# entireboard_v2_4layer.net
KiCad netlist of a schematic drawn in EAGLE
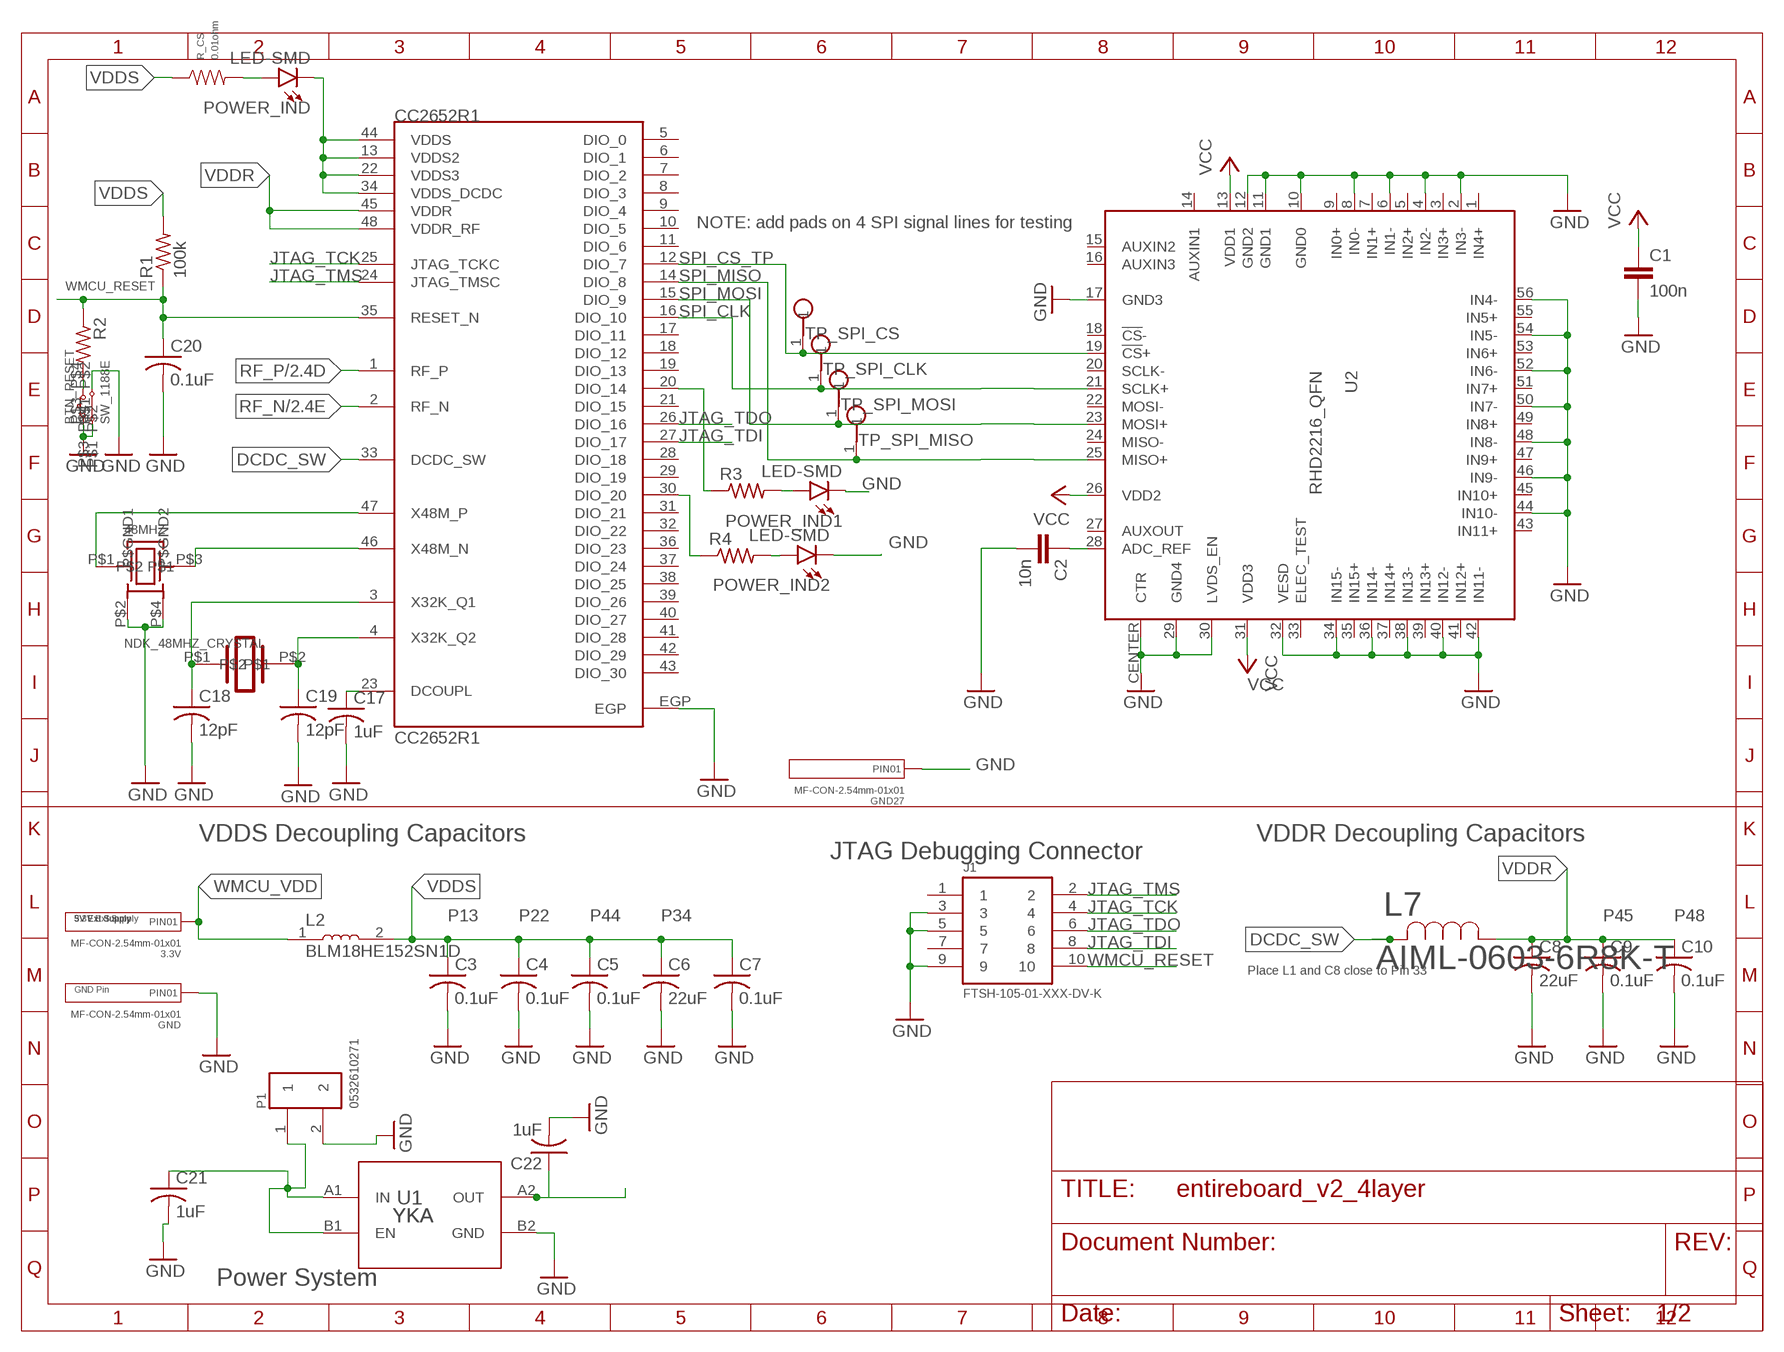
[diagram p0: schematic, sheet 1]
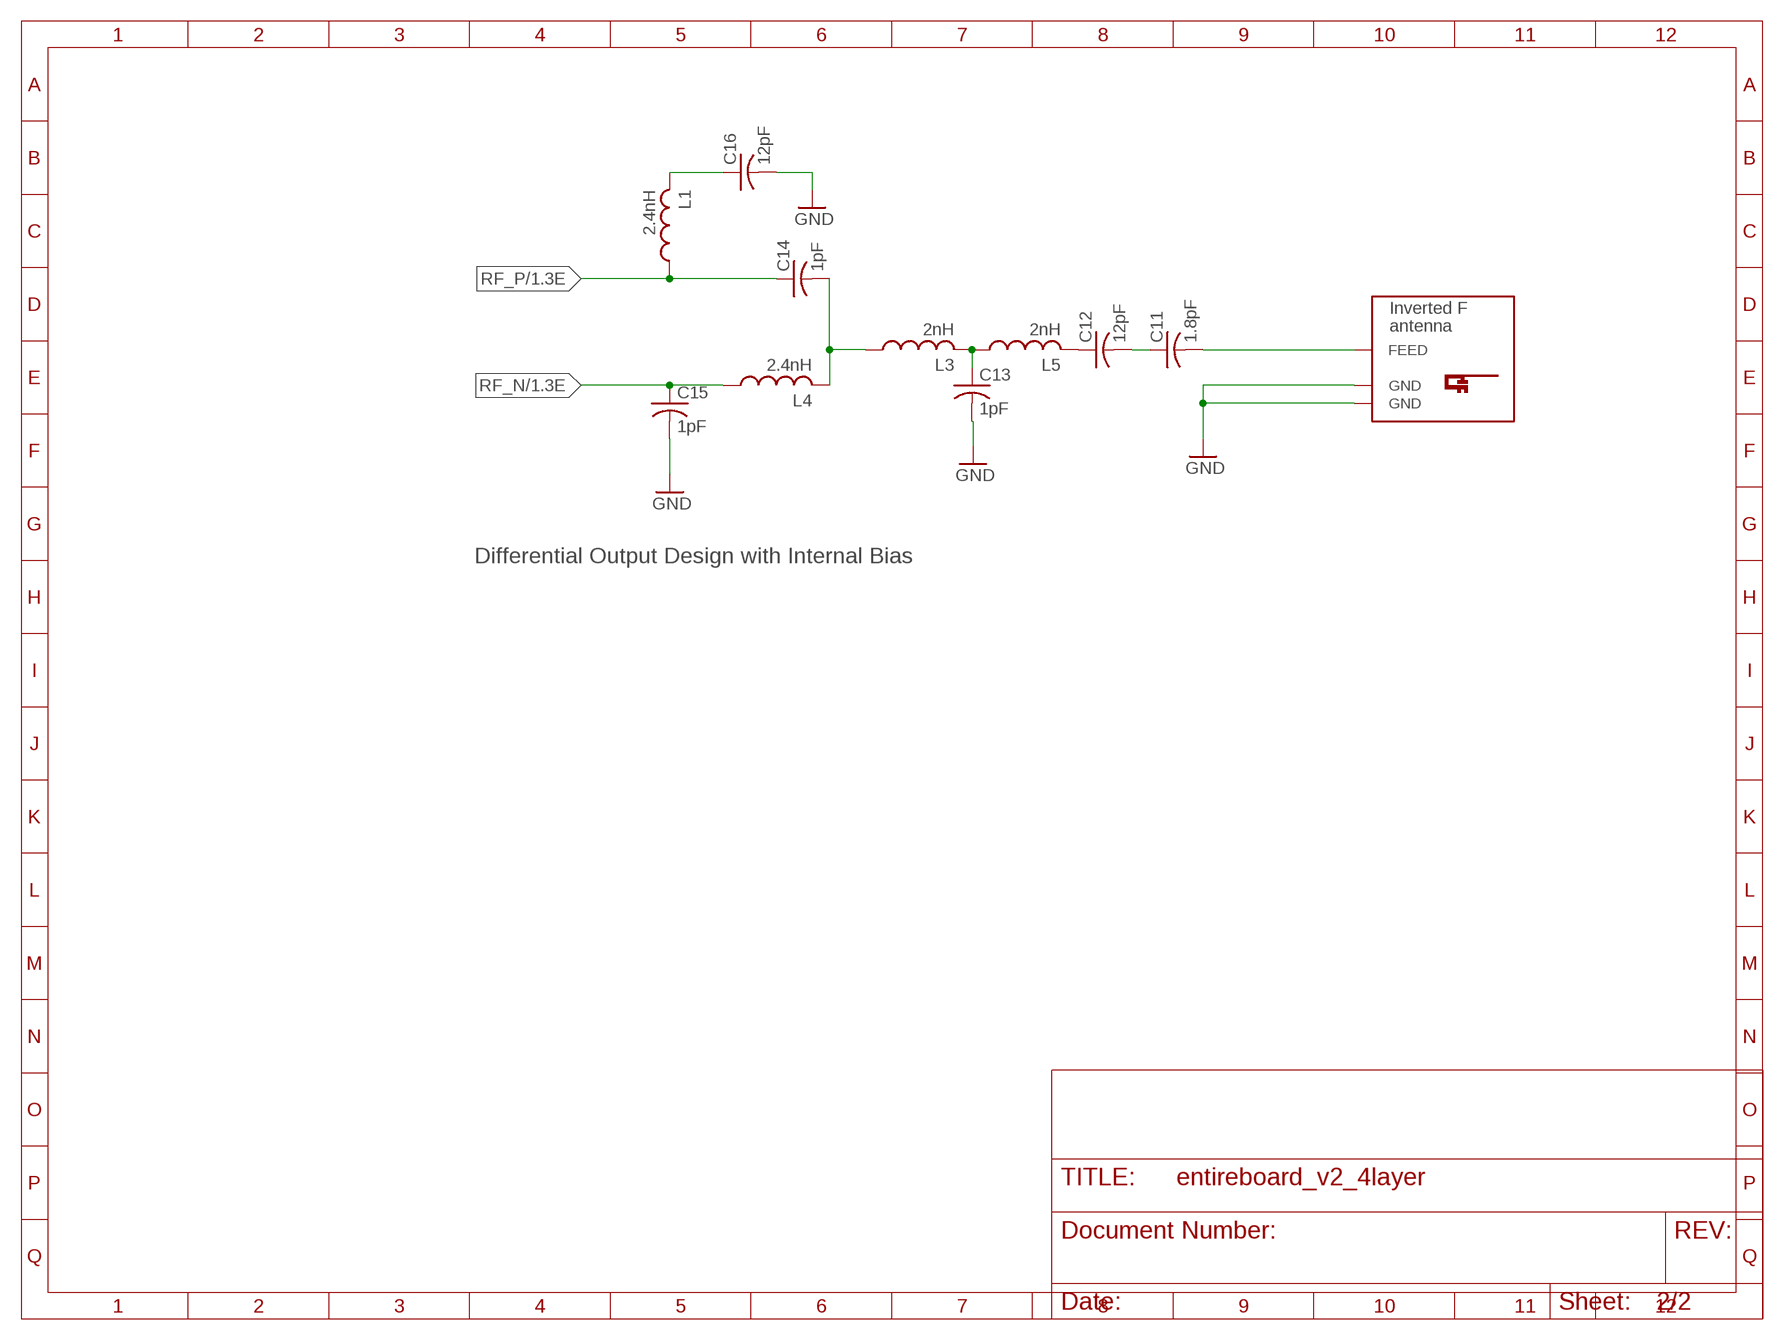
[diagram p1: schematic, sheet 2]

(export (version "E")
  (design (tool "Eeschema 10.0.6"))
  (components
    (comp (ref "C11")
      (value "1.8pF")
      (footprint "eagle-import:C0402")
      (libsource (lib "eagle-import") (part "C-USC0402"))
    )
    (comp (ref "C12")
      (value "12pF")
      (footprint "eagle-import:C0402")
      (libsource (lib "eagle-import") (part "C-USC0402"))
    )
    (comp (ref "C13")
      (value "1pF")
      (footprint "eagle-import:C0402")
      (libsource (lib "eagle-import") (part "C-USC0402"))
    )
    (comp (ref "C14")
      (value "1pF")
      (footprint "eagle-import:C0402")
      (libsource (lib "eagle-import") (part "C-USC0402"))
    )
    (comp (ref "C15")
      (value "1pF")
      (footprint "eagle-import:C0402")
      (libsource (lib "eagle-import") (part "C-USC0402"))
    )
    (comp (ref "C16")
      (value "12pF")
      (footprint "eagle-import:C0402")
      (libsource (lib "eagle-import") (part "C-USC0402"))
    )
    (comp (ref "L1")
      (value "2.4nH")
      (footprint "eagle-import:L0201")
      (libsource (lib "eagle-import") (part "L-USL0201"))
    )
    (comp (ref "L3")
      (value "2nH")
      (footprint "eagle-import:L0201")
      (libsource (lib "eagle-import") (part "L-USL0201"))
    )
    (comp (ref "L4")
      (value "2.4nH")
      (footprint "eagle-import:L0201")
      (libsource (lib "eagle-import") (part "L-USL0201"))
    )
    (comp (ref "L5")
      (value "2nH")
      (footprint "eagle-import:L0201")
      (libsource (lib "eagle-import") (part "L-USL0201"))
    )
    (comp (ref "U$2")
      (value "INVERTED_F_ANTENNA+0")
      (footprint "eagle-import:DN007+0")
      (libsource (lib "eagle-import") (part "INVERTED_F_ANTENNA+0"))
    )
    (comp (ref "3.3V")
      (value "MF-CON-2.54mm-01x01")
      (footprint "eagle-import:PTH_2.54MM_01X01")
      (fields (field (name "HOUSEPART") "YES"))
      (libsource (lib "eagle-import") (part "CON_01X01_PTH_2.54MM"))
    )
    (comp (ref "38.768KHZ")
      (value "EPSON_32.768KHZ_CRYSTAL")
      (footprint "eagle-import:2-SMD")
      (libsource (lib "eagle-import") (part "EPSON_32.768KHZ_CRYSTAL"))
    )
    (comp (ref "48MHZ")
      (value "NDK_48MHZ_CRYSTAL")
      (footprint "eagle-import:4-SMD")
      (libsource (lib "eagle-import") (part "NDK_48MHZ_CRYSTAL"))
    )
    (comp (ref "BTN_RESET")
      (value "SW_1188E")
      (footprint "eagle-import:SW_1188E")
      (libsource (lib "eagle-import") (part "SW_1188E"))
    )
    (comp (ref "C1")
      (value "100n")
      (footprint "eagle-import:0402")
      (libsource (lib "eagle-import") (part "C_0402"))
    )
    (comp (ref "C2")
      (value "10n")
      (footprint "eagle-import:0402")
      (libsource (lib "eagle-import") (part "C_0402"))
    )
    (comp (ref "C3")
      (value "0.1uF")
      (footprint "eagle-import:C0402")
      (libsource (lib "eagle-import") (part "C-USC0402"))
    )
    (comp (ref "C4")
      (value "0.1uF")
      (footprint "eagle-import:C0402")
      (libsource (lib "eagle-import") (part "C-USC0402"))
    )
    (comp (ref "C5")
      (value "0.1uF")
      (footprint "eagle-import:C0402")
      (libsource (lib "eagle-import") (part "C-USC0402"))
    )
    (comp (ref "C6")
      (value "22uF")
      (footprint "eagle-import:C0402")
      (libsource (lib "eagle-import") (part "C-USC0402"))
    )
    (comp (ref "C7")
      (value "0.1uF")
      (footprint "eagle-import:C0402")
      (libsource (lib "eagle-import") (part "C-USC0402"))
    )
    (comp (ref "C8")
      (value "22uF")
      (footprint "eagle-import:C0402")
      (libsource (lib "eagle-import") (part "C-USC0402"))
    )
    (comp (ref "C9")
      (value "0.1uF")
      (footprint "eagle-import:C0402")
      (libsource (lib "eagle-import") (part "C-USC0402"))
    )
    (comp (ref "C10")
      (value "0.1uF")
      (footprint "eagle-import:C0402")
      (libsource (lib "eagle-import") (part "C-USC0402"))
    )
    (comp (ref "C17")
      (value "1uF")
      (footprint "eagle-import:C0402")
      (libsource (lib "eagle-import") (part "C-USC0402"))
    )
    (comp (ref "C18")
      (value "12pF")
      (footprint "eagle-import:C0402")
      (libsource (lib "eagle-import") (part "C-USC0402"))
    )
    (comp (ref "C19")
      (value "12pF")
      (footprint "eagle-import:C0402")
      (libsource (lib "eagle-import") (part "C-USC0402"))
    )
    (comp (ref "C20")
      (value "0.1uF")
      (footprint "eagle-import:C0402")
      (libsource (lib "eagle-import") (part "C-USC0402"))
    )
    (comp (ref "C21")
      (value "1uF")
      (footprint "eagle-import:C0402")
      (libsource (lib "eagle-import") (part "C-USC0402"))
    )
    (comp (ref "C22")
      (value "1uF")
      (footprint "eagle-import:C0402")
      (libsource (lib "eagle-import") (part "C-USC0402"))
    )
    (comp (ref "CC2652R1")
      (value "CC2652R1")
      (footprint "eagle-import:CC2652R1_QFN-48")
      (libsource (lib "eagle-import") (part "CC2652R1"))
    )
    (comp (ref "GND")
      (value "MF-CON-2.54mm-01x01")
      (footprint "eagle-import:PTH_2.54MM_01X01")
      (fields (field (name "HOUSEPART") "YES"))
      (libsource (lib "eagle-import") (part "CON_01X01_PTH_2.54MM"))
    )
    (comp (ref "GND27")
      (value "MF-CON-2.54mm-01x01")
      (footprint "eagle-import:PTH_2.54MM_01X01")
      (fields (field (name "HOUSEPART") "YES"))
      (libsource (lib "eagle-import") (part "CON_01X01_PTH_2.54MM"))
    )
    (comp (ref "J1")
      (value "FTSH-105-01-XXX-DV-K")
      (footprint "eagle-import:FTSH-105-01-XXX-DV-K")
      (libsource (lib "eagle-import") (part "FTSH-105-01-XXX-DV-K"))
    )
    (comp (ref "L2")
      (value "BLM18HE152SN1D")
      (footprint "eagle-import:INDC1608X95")
      (fields (field (name "DIGI-KEY_PART_NUMBER") "490-5216-1-ND") (field (name "MF") "Murata Electronics"))
      (libsource (lib "eagle-import") (part "BLM18HE152SN1D"))
    )
    (comp (ref "L7")
      (value "AIML-0603-6R8K-T")
      (footprint "eagle-import:AIML-0603")
      (fields (field (name "MANUFACTURER_PART_NUMBER") "AIML06036R8KT"))
      (libsource (lib "eagle-import") (part "AIML-0603-6R8K-T"))
    )
    (comp (ref "P1")
      (value "0532610271")
      (footprint "eagle-import:MOLEX_0532610271")
      (fields (field (name "DIGI-KEY_PART_NUMBER") "WM7620CT-ND") (field (name "MF") "Molex, LLC"))
      (libsource (lib "eagle-import") (part "0532610271"))
    )
    (comp (ref "POWER_IND")
      (value "LED-SMD")
      (footprint "eagle-import:RHD2000_EVAL_BOARD_0402")
      (libsource (lib "eagle-import") (part "LED-SMD"))
    )
    (comp (ref "POWER_IND1")
      (value "LED-SMD")
      (footprint "eagle-import:RHD2000_EVAL_BOARD_0402")
      (libsource (lib "eagle-import") (part "LED-SMD"))
    )
    (comp (ref "POWER_IND2")
      (value "LED-SMD")
      (footprint "eagle-import:RHD2000_EVAL_BOARD_0402")
      (libsource (lib "eagle-import") (part "LED-SMD"))
    )
    (comp (ref "R1")
      (value "100k")
      (footprint "eagle-import:R0402")
      (libsource (lib "eagle-import") (part "R-US_R0402"))
    )
    (comp (ref "R2")
      (value "R-US_R0402")
      (footprint "eagle-import:R0402")
      (libsource (lib "eagle-import") (part "R-US_R0402"))
    )
    (comp (ref "R3")
      (value "R-US_R0402")
      (footprint "eagle-import:R0402")
      (libsource (lib "eagle-import") (part "R-US_R0402"))
    )
    (comp (ref "R4")
      (value "R-US_R0402")
      (footprint "eagle-import:R0402")
      (libsource (lib "eagle-import") (part "R-US_R0402"))
    )
    (comp (ref "R_CS")
      (value "0.01ohm")
      (footprint "eagle-import:R0402")
      (libsource (lib "eagle-import") (part "RESISTOR_0402"))
    )
    (comp (ref "TP_SPI_CLK")
      (value "RHD2000_EVAL_BOARD_TESTPOINT_SMALL")
      (footprint "eagle-import:RHD2000_EVAL_BOARD_TESTPOINT_SMALL")
      (libsource (lib "eagle-import") (part "RHD2000_EVAL_BOARD_TESTPOINT_SMALL"))
    )
    (comp (ref "TP_SPI_CS")
      (value "RHD2000_EVAL_BOARD_TESTPOINT_SMALL")
      (footprint "eagle-import:RHD2000_EVAL_BOARD_TESTPOINT_SMALL")
      (libsource (lib "eagle-import") (part "RHD2000_EVAL_BOARD_TESTPOINT_SMALL"))
    )
    (comp (ref "TP_SPI_MISO")
      (value "RHD2000_EVAL_BOARD_TESTPOINT_SMALL")
      (footprint "eagle-import:RHD2000_EVAL_BOARD_TESTPOINT_SMALL")
      (libsource (lib "eagle-import") (part "RHD2000_EVAL_BOARD_TESTPOINT_SMALL"))
    )
    (comp (ref "TP_SPI_MOSI")
      (value "RHD2000_EVAL_BOARD_TESTPOINT_SMALL")
      (footprint "eagle-import:RHD2000_EVAL_BOARD_TESTPOINT_SMALL")
      (libsource (lib "eagle-import") (part "RHD2000_EVAL_BOARD_TESTPOINT_SMALL"))
    )
    (comp (ref "U1")
      (value "YKA")
      (footprint "eagle-import:YKA0004ACAC")
      (libsource (lib "eagle-import") (part "YKA"))
    )
    (comp (ref "U2")
      (value "RHD2216_QFN")
      (footprint "eagle-import:QFN56_8_X_8_LARGE")
      (libsource (lib "eagle-import") (part "RHD2216_QFN"))
    )
  )
  (nets
    (net (code "1") (name "DCDC_SW") (class "Default")
      (node (ref "CC2652R1") (pin "33") (pinfunction "DCDC_SW_33") (pintype "bidirectional"))
      (node (ref "L7") (pin "2") (pinfunction "2_2") (pintype "passive"))
    )
    (net (code "2") (name "GND") (class "Default")
      (node (ref "48MHZ") (pin "P$2") (pinfunction "P$GND1_P$2") (pintype "bidirectional"))
      (node (ref "48MHZ") (pin "P$4") (pinfunction "P$GND2_P$4") (pintype "bidirectional"))
      (node (ref "BTN_RESET") (pin "P$1") (pinfunction "P$1_P$1") (pintype "bidirectional"))
      (node (ref "BTN_RESET") (pin "P$2") (pinfunction "P$2_P$2") (pintype "bidirectional"))
      (node (ref "BTN_RESET") (pin "P$3") (pinfunction "P$3_P$3") (pintype "bidirectional"))
      (node (ref "C1") (pin "2") (pinfunction "2_2") (pintype "passive"))
      (node (ref "C10") (pin "2") (pinfunction "2_2") (pintype "passive"))
      (node (ref "C13") (pin "2") (pinfunction "2_2") (pintype "passive"))
      (node (ref "C15") (pin "2") (pinfunction "2_2") (pintype "passive"))
      (node (ref "C16") (pin "2") (pinfunction "2_2") (pintype "passive"))
      (node (ref "C17") (pin "2") (pinfunction "2_2") (pintype "passive"))
      (node (ref "C18") (pin "2") (pinfunction "2_2") (pintype "passive"))
      (node (ref "C19") (pin "2") (pinfunction "2_2") (pintype "passive"))
      (node (ref "C2") (pin "2") (pinfunction "2_2") (pintype "passive"))
      (node (ref "C20") (pin "2") (pinfunction "2_2") (pintype "passive"))
      (node (ref "C21") (pin "2") (pinfunction "2_2") (pintype "passive"))
      (node (ref "C22") (pin "2") (pinfunction "2_2") (pintype "passive"))
      (node (ref "C3") (pin "2") (pinfunction "2_2") (pintype "passive"))
      (node (ref "C4") (pin "2") (pinfunction "2_2") (pintype "passive"))
      (node (ref "C5") (pin "2") (pinfunction "2_2") (pintype "passive"))
      (node (ref "C6") (pin "2") (pinfunction "2_2") (pintype "passive"))
      (node (ref "C7") (pin "2") (pinfunction "2_2") (pintype "passive"))
      (node (ref "C8") (pin "2") (pinfunction "2_2") (pintype "passive"))
      (node (ref "C9") (pin "2") (pinfunction "2_2") (pintype "passive"))
      (node (ref "CC2652R1") (pin "EGP") (pinfunction "EGP_EGP") (pintype "bidirectional"))
      (node (ref "GND") (pin "P$1") (pinfunction "PIN1_P$1") (pintype "bidirectional"))
      (node (ref "GND27") (pin "P$1") (pinfunction "PIN1_P$1") (pintype "bidirectional"))
      (node (ref "J1") (pin "3") (pinfunction "3_3") (pintype "bidirectional"))
      (node (ref "J1") (pin "5") (pinfunction "5_5") (pintype "bidirectional"))
      (node (ref "J1") (pin "9") (pinfunction "9_9") (pintype "bidirectional"))
      (node (ref "P1") (pin "2") (pinfunction "2_2") (pintype "passive"))
      (node (ref "POWER_IND1") (pin "2") (pinfunction "C_2") (pintype "passive"))
      (node (ref "POWER_IND2") (pin "2") (pinfunction "C_2") (pintype "passive"))
      (node (ref "U$2") (pin "GND") (pinfunction "GND_GND") (pintype "bidirectional"))
      (node (ref "U$2") (pin "GND@1") (pinfunction "GND_GND@1") (pintype "bidirectional"))
      (node (ref "U1") (pin "B2") (pinfunction "GND_B2") (pintype "power_in"))
      (node (ref "U2") (pin "10") (pinfunction "GND0_10") (pintype "input"))
      (node (ref "U2") (pin "11") (pinfunction "GND1_11") (pintype "power_in"))
      (node (ref "U2") (pin "12") (pinfunction "GND2_12") (pintype "power_in"))
      (node (ref "U2") (pin "17") (pinfunction "GND3_17") (pintype "power_in"))
      (node (ref "U2") (pin "2") (pinfunction "IN3-_2") (pintype "input"))
      (node (ref "U2") (pin "29") (pinfunction "GND4_29") (pintype "power_in"))
      (node (ref "U2") (pin "30") (pinfunction "LVDS_EN_30") (pintype "input"))
      (node (ref "U2") (pin "32") (pinfunction "VESD_32") (pintype "power_in"))
      (node (ref "U2") (pin "34") (pinfunction "IN15-_34") (pintype "input"))
      (node (ref "U2") (pin "36") (pinfunction "IN14-_36") (pintype "input"))
      (node (ref "U2") (pin "38") (pinfunction "IN13-_38") (pintype "input"))
      (node (ref "U2") (pin "4") (pinfunction "IN2-_4") (pintype "input"))
      (node (ref "U2") (pin "40") (pinfunction "IN12-_40") (pintype "input"))
      (node (ref "U2") (pin "42") (pinfunction "IN11-_42") (pintype "input"))
      (node (ref "U2") (pin "44") (pinfunction "IN10-_44") (pintype "input"))
      (node (ref "U2") (pin "46") (pinfunction "IN9-_46") (pintype "input"))
      (node (ref "U2") (pin "48") (pinfunction "IN8-_48") (pintype "input"))
      (node (ref "U2") (pin "50") (pinfunction "IN7-_50") (pintype "input"))
      (node (ref "U2") (pin "52") (pinfunction "IN6-_52") (pintype "input"))
      (node (ref "U2") (pin "54") (pinfunction "IN5-_54") (pintype "input"))
      (node (ref "U2") (pin "56") (pinfunction "IN4-_56") (pintype "input"))
      (node (ref "U2") (pin "6") (pinfunction "IN1-_6") (pintype "input"))
      (node (ref "U2") (pin "8") (pinfunction "IN0-_8") (pintype "input"))
      (node (ref "U2") (pin "CENTER") (pinfunction "CTR_CENTER") (pintype "power_in"))
    )
    (net (code "3") (name "JTAG_TCK") (class "Default")
      (node (ref "CC2652R1") (pin "25") (pinfunction "JTAG_TCKC_25") (pintype "bidirectional"))
      (node (ref "J1") (pin "4") (pinfunction "4_4") (pintype "bidirectional"))
    )
    (net (code "4") (name "JTAG_TDI") (class "Default")
      (node (ref "CC2652R1") (pin "27") (pinfunction "DIO_17_27") (pintype "bidirectional"))
      (node (ref "J1") (pin "8") (pinfunction "8_8") (pintype "bidirectional"))
    )
    (net (code "5") (name "JTAG_TDO") (class "Default")
      (node (ref "CC2652R1") (pin "26") (pinfunction "DIO_16_26") (pintype "bidirectional"))
      (node (ref "J1") (pin "6") (pinfunction "6_6") (pintype "bidirectional"))
    )
    (net (code "6") (name "JTAG_TMS") (class "Default")
      (node (ref "CC2652R1") (pin "24") (pinfunction "JTAG_TMSC_24") (pintype "bidirectional"))
      (node (ref "J1") (pin "2") (pinfunction "2_2") (pintype "bidirectional"))
    )
    (net (code "7") (name "Net-(48MHZ-P$2)") (class "Default")
      (node (ref "48MHZ") (pin "P$3") (pinfunction "P$2_P$3") (pintype "bidirectional"))
      (node (ref "CC2652R1") (pin "46") (pinfunction "X48M_N_46") (pintype "bidirectional"))
    )
    (net (code "8") (name "Net-(BTN_RESET-PadP$4)") (class "Default")
      (node (ref "BTN_RESET") (pin "P$4") (pinfunction "P$4_P$4") (pintype "bidirectional"))
      (node (ref "R2") (pin "2") (pinfunction "2_2") (pintype "passive"))
    )
    (net (code "9") (name "Net-(C11-Pad1)") (class "Default")
      (node (ref "C11") (pin "1") (pinfunction "1_1") (pintype "passive"))
      (node (ref "C12") (pin "2") (pinfunction "2_2") (pintype "passive"))
    )
    (net (code "10") (name "Net-(C11-Pad2)") (class "Default")
      (node (ref "C11") (pin "2") (pinfunction "2_2") (pintype "passive"))
      (node (ref "U$2") (pin "FEED") (pinfunction "FEED_FEED") (pintype "bidirectional"))
    )
    (net (code "11") (name "Net-(C12-Pad1)") (class "Default")
      (node (ref "C12") (pin "1") (pinfunction "1_1") (pintype "passive"))
      (node (ref "L5") (pin "2") (pinfunction "2_2") (pintype "passive"))
    )
    (net (code "12") (name "Net-(C13-Pad1)") (class "Default")
      (node (ref "C13") (pin "1") (pinfunction "1_1") (pintype "passive"))
      (node (ref "L3") (pin "2") (pinfunction "2_2") (pintype "passive"))
      (node (ref "L5") (pin "1") (pinfunction "1_1") (pintype "passive"))
    )
    (net (code "13") (name "Net-(C14-Pad2)") (class "Default")
      (node (ref "C14") (pin "2") (pinfunction "2_2") (pintype "passive"))
      (node (ref "L3") (pin "1") (pinfunction "1_1") (pintype "passive"))
      (node (ref "L4") (pin "2") (pinfunction "2_2") (pintype "passive"))
    )
    (net (code "14") (name "Net-(C16-Pad1)") (class "Default")
      (node (ref "C16") (pin "1") (pinfunction "1_1") (pintype "passive"))
      (node (ref "L1") (pin "2") (pinfunction "2_2") (pintype "passive"))
    )
    (net (code "15") (name "Net-(CC2652R1-DCOUPL)") (class "Default")
      (node (ref "C17") (pin "1") (pinfunction "1_1") (pintype "passive"))
      (node (ref "CC2652R1") (pin "23") (pinfunction "DCOUPL_23") (pintype "bidirectional"))
    )
    (net (code "16") (name "Net-(CC2652R1-DIO_14)") (class "Default")
      (node (ref "CC2652R1") (pin "20") (pinfunction "DIO_14_20") (pintype "bidirectional"))
      (node (ref "R3") (pin "1") (pinfunction "1_1") (pintype "passive"))
    )
    (net (code "17") (name "Net-(CC2652R1-DIO_20)") (class "Default")
      (node (ref "CC2652R1") (pin "30") (pinfunction "DIO_20_30") (pintype "bidirectional"))
      (node (ref "R4") (pin "1") (pinfunction "1_1") (pintype "passive"))
    )
    (net (code "18") (name "Net-(CC2652R1-X32K_Q1)") (class "Default")
      (node (ref "38.768KHZ") (pin "P$1") (pinfunction "P$1_P$1") (pintype "bidirectional"))
      (node (ref "C18") (pin "1") (pinfunction "1_1") (pintype "passive"))
      (node (ref "CC2652R1") (pin "3") (pinfunction "X32K_Q1_3") (pintype "bidirectional"))
    )
    (net (code "19") (name "Net-(CC2652R1-X32K_Q2)") (class "Default")
      (node (ref "38.768KHZ") (pin "P$2") (pinfunction "P$2_P$2") (pintype "bidirectional"))
      (node (ref "C19") (pin "1") (pinfunction "1_1") (pintype "passive"))
      (node (ref "CC2652R1") (pin "4") (pinfunction "X32K_Q2_4") (pintype "bidirectional"))
    )
    (net (code "20") (name "Net-(CC2652R1-X48M_P)") (class "Default")
      (node (ref "48MHZ") (pin "P$1") (pinfunction "P$1_P$1") (pintype "bidirectional"))
      (node (ref "CC2652R1") (pin "47") (pinfunction "X48M_P_47") (pintype "bidirectional"))
    )
    (net (code "21") (name "Net-(POWER_IND-A)") (class "Default")
      (node (ref "POWER_IND") (pin "1") (pinfunction "A_1") (pintype "passive"))
      (node (ref "R_CS") (pin "P$2") (pinfunction "P$2_P$2") (pintype "passive"))
    )
    (net (code "22") (name "Net-(POWER_IND1-A)") (class "Default")
      (node (ref "POWER_IND1") (pin "1") (pinfunction "A_1") (pintype "passive"))
      (node (ref "R3") (pin "2") (pinfunction "2_2") (pintype "passive"))
    )
    (net (code "23") (name "Net-(POWER_IND2-A)") (class "Default")
      (node (ref "POWER_IND2") (pin "1") (pinfunction "A_1") (pintype "passive"))
      (node (ref "R4") (pin "2") (pinfunction "2_2") (pintype "passive"))
    )
    (net (code "24") (name "Net-(U1-EN)") (class "Default")
      (node (ref "C21") (pin "1") (pinfunction "1_1") (pintype "passive"))
      (node (ref "P1") (pin "1") (pinfunction "1_1") (pintype "passive"))
      (node (ref "U1") (pin "A1") (pinfunction "IN_A1") (pintype "power_in"))
      (node (ref "U1") (pin "B1") (pinfunction "EN_B1") (pintype "input"))
    )
    (net (code "25") (name "Net-(U2-ADC_REF)") (class "Default")
      (node (ref "C2") (pin "1") (pinfunction "1_1") (pintype "passive"))
      (node (ref "U2") (pin "28") (pinfunction "ADC_REF_28") (pintype "passive"))
    )
    (net (code "26") (name "RF_N") (class "Default")
      (node (ref "C15") (pin "1") (pinfunction "1_1") (pintype "passive"))
      (node (ref "CC2652R1") (pin "2") (pinfunction "RF_N_2") (pintype "bidirectional"))
      (node (ref "L4") (pin "1") (pinfunction "1_1") (pintype "passive"))
    )
    (net (code "27") (name "RF_P") (class "Default")
      (node (ref "C14") (pin "1") (pinfunction "1_1") (pintype "passive"))
      (node (ref "CC2652R1") (pin "1") (pinfunction "RF_P_1") (pintype "bidirectional"))
      (node (ref "L1") (pin "1") (pinfunction "1_1") (pintype "passive"))
    )
    (net (code "28") (name "SPI_CLK") (class "Default")
      (node (ref "CC2652R1") (pin "16") (pinfunction "DIO_10_16") (pintype "bidirectional"))
      (node (ref "TP_SPI_CLK") (pin "1") (pinfunction "1_1") (pintype "passive"))
      (node (ref "U2") (pin "21") (pinfunction "SCLK+_21") (pintype "input"))
    )
    (net (code "29") (name "SPI_CS_TP") (class "Default")
      (node (ref "CC2652R1") (pin "12") (pinfunction "DIO_7_12") (pintype "bidirectional"))
      (node (ref "TP_SPI_CS") (pin "1") (pinfunction "1_1") (pintype "passive"))
      (node (ref "U2") (pin "19") (pinfunction "~{CS}+_19") (pintype "input"))
    )
    (net (code "30") (name "SPI_MISO") (class "Default")
      (node (ref "CC2652R1") (pin "14") (pinfunction "DIO_8_14") (pintype "bidirectional"))
      (node (ref "TP_SPI_MISO") (pin "1") (pinfunction "1_1") (pintype "passive"))
      (node (ref "U2") (pin "25") (pinfunction "MISO+_25") (pintype "output"))
    )
    (net (code "31") (name "SPI_MOSI") (class "Default")
      (node (ref "CC2652R1") (pin "15") (pinfunction "DIO_9_15") (pintype "bidirectional"))
      (node (ref "TP_SPI_MOSI") (pin "1") (pinfunction "1_1") (pintype "passive"))
      (node (ref "U2") (pin "23") (pinfunction "MOSI+_23") (pintype "input"))
    )
    (net (code "32") (name "VCC") (class "Default")
      (node (ref "C1") (pin "1") (pinfunction "1_1") (pintype "passive"))
      (node (ref "U2") (pin "13") (pinfunction "VDD1_13") (pintype "power_in"))
      (node (ref "U2") (pin "26") (pinfunction "VDD2_26") (pintype "power_in"))
      (node (ref "U2") (pin "31") (pinfunction "VDD3_31") (pintype "power_in"))
    )
    (net (code "33") (name "VDDR") (class "Default")
      (node (ref "C10") (pin "1") (pinfunction "1_1") (pintype "passive"))
      (node (ref "C8") (pin "1") (pinfunction "1_1") (pintype "passive"))
      (node (ref "C9") (pin "1") (pinfunction "1_1") (pintype "passive"))
      (node (ref "CC2652R1") (pin "45") (pinfunction "VDDR_45") (pintype "bidirectional"))
      (node (ref "CC2652R1") (pin "48") (pinfunction "VDDR_RF_48") (pintype "bidirectional"))
      (node (ref "L7") (pin "1") (pinfunction "1_1") (pintype "passive"))
    )
    (net (code "34") (name "VDDS") (class "Default")
      (node (ref "C3") (pin "1") (pinfunction "1_1") (pintype "passive"))
      (node (ref "C4") (pin "1") (pinfunction "1_1") (pintype "passive"))
      (node (ref "C5") (pin "1") (pinfunction "1_1") (pintype "passive"))
      (node (ref "C6") (pin "1") (pinfunction "1_1") (pintype "passive"))
      (node (ref "C7") (pin "1") (pinfunction "1_1") (pintype "passive"))
      (node (ref "CC2652R1") (pin "13") (pinfunction "VDDS2_13") (pintype "bidirectional"))
      (node (ref "CC2652R1") (pin "22") (pinfunction "VDDS3_22") (pintype "bidirectional"))
      (node (ref "CC2652R1") (pin "34") (pinfunction "VDDS_DCDC_34") (pintype "bidirectional"))
      (node (ref "CC2652R1") (pin "44") (pinfunction "VDDS_44") (pintype "bidirectional"))
      (node (ref "L2") (pin "2") (pinfunction "2_2") (pintype "passive"))
      (node (ref "POWER_IND") (pin "2") (pinfunction "C_2") (pintype "passive"))
      (node (ref "R1") (pin "2") (pinfunction "2_2") (pintype "passive"))
      (node (ref "R_CS") (pin "P$1") (pinfunction "P$1_P$1") (pintype "passive"))
    )
    (net (code "35") (name "WMCU_RESET") (class "Default")
      (node (ref "C20") (pin "1") (pinfunction "1_1") (pintype "passive"))
      (node (ref "CC2652R1") (pin "35") (pinfunction "RESET_N_35") (pintype "bidirectional"))
      (node (ref "J1") (pin "10") (pinfunction "10_10") (pintype "bidirectional"))
      (node (ref "R1") (pin "1") (pinfunction "1_1") (pintype "passive"))
      (node (ref "R2") (pin "1") (pinfunction "1_1") (pintype "passive"))
    )
    (net (code "36") (name "WMCU_VDD") (class "Default")
      (node (ref "3.3V") (pin "P$1") (pinfunction "PIN1_P$1") (pintype "bidirectional"))
      (node (ref "C22") (pin "1") (pinfunction "1_1") (pintype "passive"))
      (node (ref "L2") (pin "1") (pinfunction "1_1") (pintype "passive"))
      (node (ref "U1") (pin "A2") (pinfunction "OUT_A2") (pintype "power_in"))
    )
    (net (code "37") (name "unconnected-(CC2652R1-DIO_0-Pad5)") (class "Default")
      (node (ref "CC2652R1") (pin "5") (pinfunction "DIO_0_5") (pintype "bidirectional"))
    )
    (net (code "38") (name "unconnected-(CC2652R1-DIO_1-Pad6)") (class "Default")
      (node (ref "CC2652R1") (pin "6") (pinfunction "DIO_1_6") (pintype "bidirectional"))
    )
    (net (code "39") (name "unconnected-(CC2652R1-DIO_2-Pad7)") (class "Default")
      (node (ref "CC2652R1") (pin "7") (pinfunction "DIO_2_7") (pintype "bidirectional"))
    )
    (net (code "40") (name "unconnected-(CC2652R1-DIO_3-Pad8)") (class "Default")
      (node (ref "CC2652R1") (pin "8") (pinfunction "DIO_3_8") (pintype "bidirectional"))
    )
    (net (code "41") (name "unconnected-(CC2652R1-DIO_4-Pad9)") (class "Default")
      (node (ref "CC2652R1") (pin "9") (pinfunction "DIO_4_9") (pintype "bidirectional"))
    )
    (net (code "42") (name "unconnected-(CC2652R1-DIO_5-Pad10)") (class "Default")
      (node (ref "CC2652R1") (pin "10") (pinfunction "DIO_5_10") (pintype "bidirectional"))
    )
    (net (code "43") (name "unconnected-(CC2652R1-DIO_6-Pad11)") (class "Default")
      (node (ref "CC2652R1") (pin "11") (pinfunction "DIO_6_11") (pintype "bidirectional"))
    )
    (net (code "44") (name "unconnected-(CC2652R1-DIO_11-Pad17)") (class "Default")
      (node (ref "CC2652R1") (pin "17") (pinfunction "DIO_11_17") (pintype "bidirectional"))
    )
    (net (code "45") (name "unconnected-(CC2652R1-DIO_12-Pad18)") (class "Default")
      (node (ref "CC2652R1") (pin "18") (pinfunction "DIO_12_18") (pintype "bidirectional"))
    )
    (net (code "46") (name "unconnected-(CC2652R1-DIO_13-Pad19)") (class "Default")
      (node (ref "CC2652R1") (pin "19") (pinfunction "DIO_13_19") (pintype "bidirectional"))
    )
    (net (code "47") (name "unconnected-(CC2652R1-DIO_15-Pad21)") (class "Default")
      (node (ref "CC2652R1") (pin "21") (pinfunction "DIO_15_21") (pintype "bidirectional"))
    )
    (net (code "48") (name "unconnected-(CC2652R1-DIO_18-Pad28)") (class "Default")
      (node (ref "CC2652R1") (pin "28") (pinfunction "DIO_18_28") (pintype "bidirectional"))
    )
    (net (code "49") (name "unconnected-(CC2652R1-DIO_19-Pad29)") (class "Default")
      (node (ref "CC2652R1") (pin "29") (pinfunction "DIO_19_29") (pintype "bidirectional"))
    )
    (net (code "50") (name "unconnected-(CC2652R1-DIO_21-Pad31)") (class "Default")
      (node (ref "CC2652R1") (pin "31") (pinfunction "DIO_21_31") (pintype "bidirectional"))
    )
    (net (code "51") (name "unconnected-(CC2652R1-DIO_22-Pad32)") (class "Default")
      (node (ref "CC2652R1") (pin "32") (pinfunction "DIO_22_32") (pintype "bidirectional"))
    )
    (net (code "52") (name "unconnected-(CC2652R1-DIO_23-Pad36)") (class "Default")
      (node (ref "CC2652R1") (pin "36") (pinfunction "DIO_23_36") (pintype "bidirectional"))
    )
    (net (code "53") (name "unconnected-(CC2652R1-DIO_24-Pad37)") (class "Default")
      (node (ref "CC2652R1") (pin "37") (pinfunction "DIO_24_37") (pintype "bidirectional"))
    )
    (net (code "54") (name "unconnected-(CC2652R1-DIO_25-Pad38)") (class "Default")
      (node (ref "CC2652R1") (pin "38") (pinfunction "DIO_25_38") (pintype "bidirectional"))
    )
    (net (code "55") (name "unconnected-(CC2652R1-DIO_26-Pad39)") (class "Default")
      (node (ref "CC2652R1") (pin "39") (pinfunction "DIO_26_39") (pintype "bidirectional"))
    )
    (net (code "56") (name "unconnected-(CC2652R1-DIO_27-Pad40)") (class "Default")
      (node (ref "CC2652R1") (pin "40") (pinfunction "DIO_27_40") (pintype "bidirectional"))
    )
    (net (code "57") (name "unconnected-(CC2652R1-DIO_28-Pad41)") (class "Default")
      (node (ref "CC2652R1") (pin "41") (pinfunction "DIO_28_41") (pintype "bidirectional"))
    )
    (net (code "58") (name "unconnected-(CC2652R1-DIO_29-Pad42)") (class "Default")
      (node (ref "CC2652R1") (pin "42") (pinfunction "DIO_29_42") (pintype "bidirectional"))
    )
    (net (code "59") (name "unconnected-(CC2652R1-DIO_30-Pad43)") (class "Default")
      (node (ref "CC2652R1") (pin "43") (pinfunction "DIO_30_43") (pintype "bidirectional"))
    )
    (net (code "60") (name "unconnected-(J1-Pad1)") (class "Default")
      (node (ref "J1") (pin "1") (pinfunction "1_1") (pintype "bidirectional"))
    )
    (net (code "61") (name "unconnected-(J1-Pad7)") (class "Default")
      (node (ref "J1") (pin "7") (pinfunction "7_7") (pintype "bidirectional"))
    )
    (net (code "62") (name "unconnected-(U2-AUXIN1-Pad14)") (class "Default")
      (node (ref "U2") (pin "14") (pinfunction "AUXIN1_14") (pintype "input"))
    )
    (net (code "63") (name "unconnected-(U2-AUXIN2-Pad15)") (class "Default")
      (node (ref "U2") (pin "15") (pinfunction "AUXIN2_15") (pintype "input"))
    )
    (net (code "64") (name "unconnected-(U2-AUXIN3-Pad16)") (class "Default")
      (node (ref "U2") (pin "16") (pinfunction "AUXIN3_16") (pintype "input"))
    )
    (net (code "65") (name "unconnected-(U2-AUXOUT-Pad27)") (class "Default")
      (node (ref "U2") (pin "27") (pinfunction "AUXOUT_27") (pintype "tri_state"))
    )
    (net (code "66") (name "unconnected-(U2-ELEC_TEST-Pad33)") (class "Default")
      (node (ref "U2") (pin "33") (pinfunction "ELEC_TEST_33") (pintype "input"))
    )
    (net (code "67") (name "unconnected-(U2-IN0+-Pad9)") (class "Default")
      (node (ref "U2") (pin "9") (pinfunction "IN0+_9") (pintype "input"))
    )
    (net (code "68") (name "unconnected-(U2-IN1+-Pad7)") (class "Default")
      (node (ref "U2") (pin "7") (pinfunction "IN1+_7") (pintype "input"))
    )
    (net (code "69") (name "unconnected-(U2-IN2+-Pad5)") (class "Default")
      (node (ref "U2") (pin "5") (pinfunction "IN2+_5") (pintype "input"))
    )
    (net (code "70") (name "unconnected-(U2-IN3+-Pad3)") (class "Default")
      (node (ref "U2") (pin "3") (pinfunction "IN3+_3") (pintype "input"))
    )
    (net (code "71") (name "unconnected-(U2-IN4+-Pad1)") (class "Default")
      (node (ref "U2") (pin "1") (pinfunction "IN4+_1") (pintype "input"))
    )
    (net (code "72") (name "unconnected-(U2-IN5+-Pad55)") (class "Default")
      (node (ref "U2") (pin "55") (pinfunction "IN5+_55") (pintype "input"))
    )
    (net (code "73") (name "unconnected-(U2-IN6+-Pad53)") (class "Default")
      (node (ref "U2") (pin "53") (pinfunction "IN6+_53") (pintype "input"))
    )
    (net (code "74") (name "unconnected-(U2-IN7+-Pad51)") (class "Default")
      (node (ref "U2") (pin "51") (pinfunction "IN7+_51") (pintype "input"))
    )
    (net (code "75") (name "unconnected-(U2-IN8+-Pad49)") (class "Default")
      (node (ref "U2") (pin "49") (pinfunction "IN8+_49") (pintype "input"))
    )
    (net (code "76") (name "unconnected-(U2-IN9+-Pad47)") (class "Default")
      (node (ref "U2") (pin "47") (pinfunction "IN9+_47") (pintype "input"))
    )
    (net (code "77") (name "unconnected-(U2-IN10+-Pad45)") (class "Default")
      (node (ref "U2") (pin "45") (pinfunction "IN10+_45") (pintype "input"))
    )
    (net (code "78") (name "unconnected-(U2-IN11+-Pad43)") (class "Default")
      (node (ref "U2") (pin "43") (pinfunction "IN11+_43") (pintype "input"))
    )
    (net (code "79") (name "unconnected-(U2-IN12+-Pad41)") (class "Default")
      (node (ref "U2") (pin "41") (pinfunction "IN12+_41") (pintype "input"))
    )
    (net (code "80") (name "unconnected-(U2-IN13+-Pad39)") (class "Default")
      (node (ref "U2") (pin "39") (pinfunction "IN13+_39") (pintype "input"))
    )
    (net (code "81") (name "unconnected-(U2-IN14+-Pad37)") (class "Default")
      (node (ref "U2") (pin "37") (pinfunction "IN14+_37") (pintype "input"))
    )
    (net (code "82") (name "unconnected-(U2-IN15+-Pad35)") (class "Default")
      (node (ref "U2") (pin "35") (pinfunction "IN15+_35") (pintype "input"))
    )
    (net (code "83") (name "unconnected-(U2-MISO--Pad24)") (class "Default")
      (node (ref "U2") (pin "24") (pinfunction "MISO-_24") (pintype "output"))
    )
    (net (code "84") (name "unconnected-(U2-MOSI--Pad22)") (class "Default")
      (node (ref "U2") (pin "22") (pinfunction "MOSI-_22") (pintype "input"))
    )
    (net (code "85") (name "unconnected-(U2-SCLK--Pad20)") (class "Default")
      (node (ref "U2") (pin "20") (pinfunction "SCLK-_20") (pintype "input"))
    )
    (net (code "86") (name "unconnected-(U2-~{CS}--Pad18)") (class "Default")
      (node (ref "U2") (pin "18") (pinfunction "~{CS}-_18") (pintype "input"))
    )
  )
)
